# AMU-S17-V00-BSPDWindowComparitor.net
KiCad netlist of a schematic drawn in Altium Designer
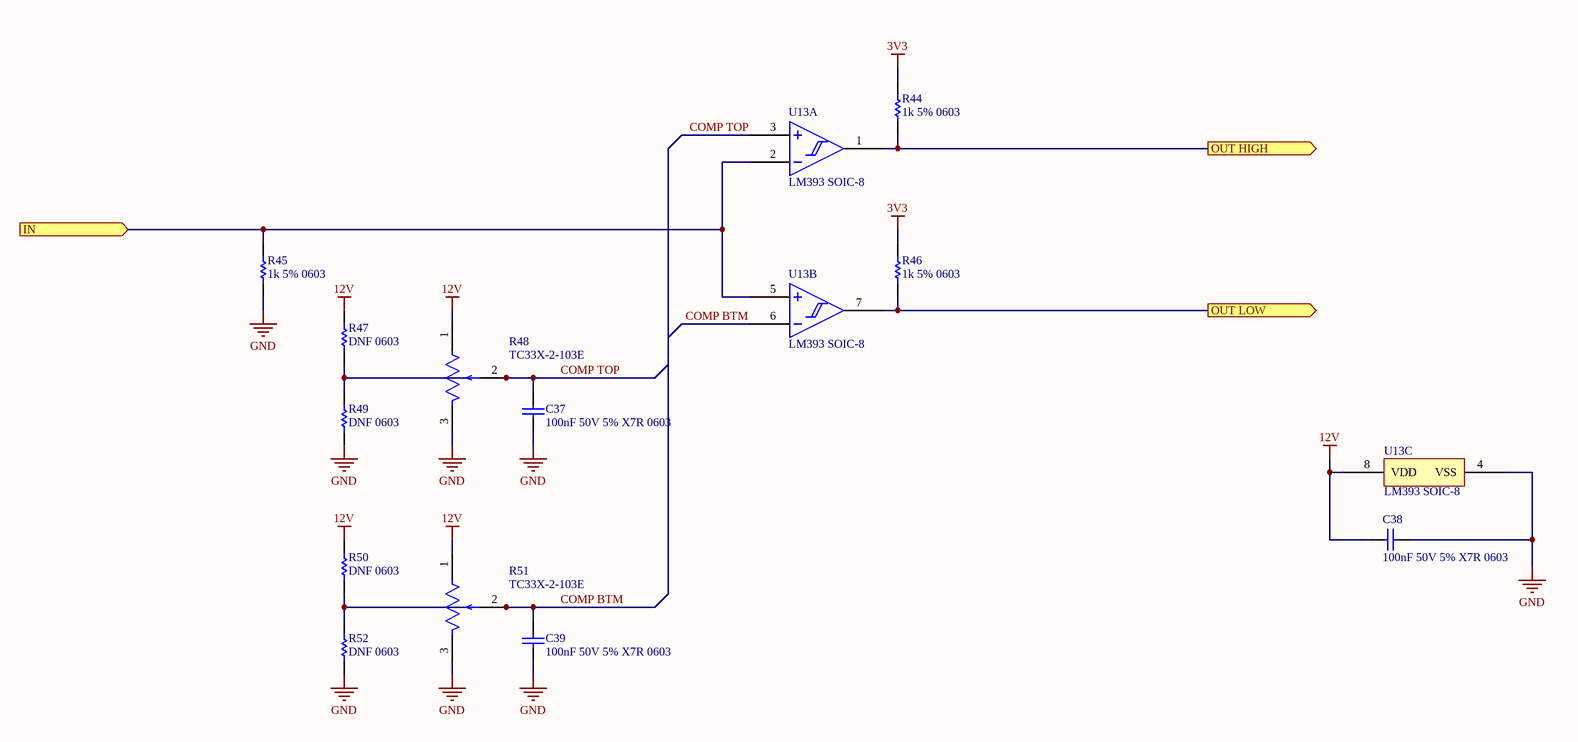
[diagram p0: AMU-S17-V00-BSPDWindowComparitor.SchDoc]

(export (version "E")
  (design (tool "Eeschema 10.0.6"))
  (components
    (comp (ref "C37")
      (value "100nF 50V 5% X7R 0603")
      (footprint "Cap_Ceramic_0603")
      (description "Capacitor, Ceramic, SMD, 100nF, 50V, 5%, X7R, 0603")
      (libsource (lib "StandardCapacitors") (part "100nF 50V 5% X7R 0603"))
    )
    (comp (ref "C38")
      (value "100nF 50V 5% X7R 0603")
      (footprint "Cap_Ceramic_0603")
      (description "Capacitor, Ceramic, SMD, 100nF, 50V, 5%, X7R, 0603")
      (libsource (lib "StandardCapacitors") (part "100nF 50V 5% X7R 0603"))
    )
    (comp (ref "C39")
      (value "100nF 50V 5% X7R 0603")
      (footprint "Cap_Ceramic_0603")
      (description "Capacitor, Ceramic, SMD, 100nF, 50V, 5%, X7R, 0603")
      (libsource (lib "StandardCapacitors") (part "100nF 50V 5% X7R 0603"))
    )
    (comp (ref "R44")
      (value "1k 5% 0603")
      (footprint "Res_ThinFilm_0603")
      (description "Resistor, SMD, 1k, 0.1W, 5%, 0603")
      (libsource (lib "StandardResistors") (part "1k 5% 0603"))
    )
    (comp (ref "R45")
      (value "1k 5% 0603")
      (footprint "Res_ThinFilm_0603")
      (description "Resistor, SMD, 1k, 0.1W, 5%, 0603")
      (libsource (lib "StandardResistors") (part "1k 5% 0603"))
    )
    (comp (ref "R46")
      (value "1k 5% 0603")
      (footprint "Res_ThinFilm_0603")
      (description "Resistor, SMD, 1k, 0.1W, 5%, 0603")
      (libsource (lib "StandardResistors") (part "1k 5% 0603"))
    )
    (comp (ref "R47")
      (value "DNF 0603")
      (footprint "Res_ThinFilm_0603")
      (description "Resistor, SMD, DNF, 0.1W, 0603")
      (libsource (lib "StandardResistors") (part "DNF 0603"))
    )
    (comp (ref "R48")
      (value "TC33X-2-103E")
      (footprint "TC33")
      (description "10 kOhms 0.1W, 1/10W J Lead Surface Mount Trimmer Potentiometer Cermet 1 Turn Top Adjustment")
      (libsource (lib "QUTMS_TrimmerLibrary") (part "TC33X-2-103E"))
    )
    (comp (ref "R49")
      (value "DNF 0603")
      (footprint "Res_ThinFilm_0603")
      (description "Resistor, SMD, DNF, 0.1W, 0603")
      (libsource (lib "StandardResistors") (part "DNF 0603"))
    )
    (comp (ref "R50")
      (value "DNF 0603")
      (footprint "Res_ThinFilm_0603")
      (description "Resistor, SMD, DNF, 0.1W, 0603")
      (libsource (lib "StandardResistors") (part "DNF 0603"))
    )
    (comp (ref "R51")
      (value "TC33X-2-103E")
      (footprint "TC33")
      (description "10 kOhms 0.1W, 1/10W J Lead Surface Mount Trimmer Potentiometer Cermet 1 Turn Top Adjustment")
      (libsource (lib "QUTMS_TrimmerLibrary") (part "TC33X-2-103E"))
    )
    (comp (ref "R52")
      (value "DNF 0603")
      (footprint "Res_ThinFilm_0603")
      (description "Resistor, SMD, DNF, 0.1W, 0603")
      (libsource (lib "StandardResistors") (part "DNF 0603"))
    )
    (comp (ref "U13")
      (value "LM393 SOIC-8")
      (footprint "SOIC-8")
      (description "General Purpose Comparitor 2 Circuit 8-SOIC")
      (libsource (lib "QUTMS_OpAmpLibrary") (part "LM393"))
    )
  )
  (nets
    (net (code "1") (name "/COMP BTM") (class "Default")
      (node (ref "C39") (pin "2") (pinfunction "2_2") (pintype "passive"))
      (node (ref "R50") (pin "1") (pinfunction "1_1") (pintype "passive"))
      (node (ref "R51") (pin "2") (pinfunction "2_2") (pintype "passive"))
      (node (ref "R52") (pin "2") (pinfunction "2_2") (pintype "passive"))
      (node (ref "U13") (pin "6") (pinfunction "IN2-_6") (pintype "passive"))
    )
    (net (code "2") (name "/COMP TOP") (class "Default")
      (node (ref "C37") (pin "2") (pinfunction "2_2") (pintype "passive"))
      (node (ref "R47") (pin "1") (pinfunction "1_1") (pintype "passive"))
      (node (ref "R48") (pin "2") (pinfunction "2_2") (pintype "passive"))
      (node (ref "R49") (pin "2") (pinfunction "2_2") (pintype "passive"))
      (node (ref "U13") (pin "3") (pinfunction "IN1+_3") (pintype "passive"))
    )
    (net (code "3") (name "/IN") (class "Default")
      (node (ref "R45") (pin "2") (pinfunction "2_2") (pintype "passive"))
      (node (ref "U13") (pin "2") (pinfunction "IN1-_2") (pintype "passive"))
      (node (ref "U13") (pin "5") (pinfunction "IN2+_5") (pintype "passive"))
    )
    (net (code "4") (name "/OUT HIGH") (class "Default")
      (node (ref "R44") (pin "1") (pinfunction "1_1") (pintype "passive"))
      (node (ref "U13") (pin "1") (pinfunction "OUT1_1") (pintype "passive"))
    )
    (net (code "5") (name "/OUT LOW") (class "Default")
      (node (ref "R46") (pin "1") (pinfunction "1_1") (pintype "passive"))
      (node (ref "U13") (pin "7") (pinfunction "OUT1_7") (pintype "passive"))
    )
    (net (code "6") (name "3V3") (class "Default")
      (node (ref "R44") (pin "2") (pinfunction "2_2") (pintype "passive"))
      (node (ref "R46") (pin "2") (pinfunction "2_2") (pintype "passive"))
    )
    (net (code "7") (name "12V") (class "Default")
      (node (ref "C38") (pin "1") (pinfunction "1_1") (pintype "passive"))
      (node (ref "R47") (pin "2") (pinfunction "2_2") (pintype "passive"))
      (node (ref "R48") (pin "1") (pinfunction "1_1") (pintype "passive"))
      (node (ref "R50") (pin "2") (pinfunction "2_2") (pintype "passive"))
      (node (ref "R51") (pin "1") (pinfunction "1_1") (pintype "passive"))
      (node (ref "U13") (pin "8") (pinfunction "VDD_8") (pintype "passive"))
    )
    (net (code "8") (name "GND") (class "Default")
      (node (ref "C37") (pin "1") (pinfunction "1_1") (pintype "passive"))
      (node (ref "C38") (pin "2") (pinfunction "2_2") (pintype "passive"))
      (node (ref "C39") (pin "1") (pinfunction "1_1") (pintype "passive"))
      (node (ref "R45") (pin "1") (pinfunction "1_1") (pintype "passive"))
      (node (ref "R48") (pin "3") (pinfunction "3_3") (pintype "passive"))
      (node (ref "R49") (pin "1") (pinfunction "1_1") (pintype "passive"))
      (node (ref "R51") (pin "3") (pinfunction "3_3") (pintype "passive"))
      (node (ref "R52") (pin "1") (pinfunction "1_1") (pintype "passive"))
      (node (ref "U13") (pin "4") (pinfunction "VSS_4") (pintype "passive"))
    )
  )
)
